# CW308T_STM32F415_Micro.net
KiCad netlist of a schematic drawn in Altium Designer
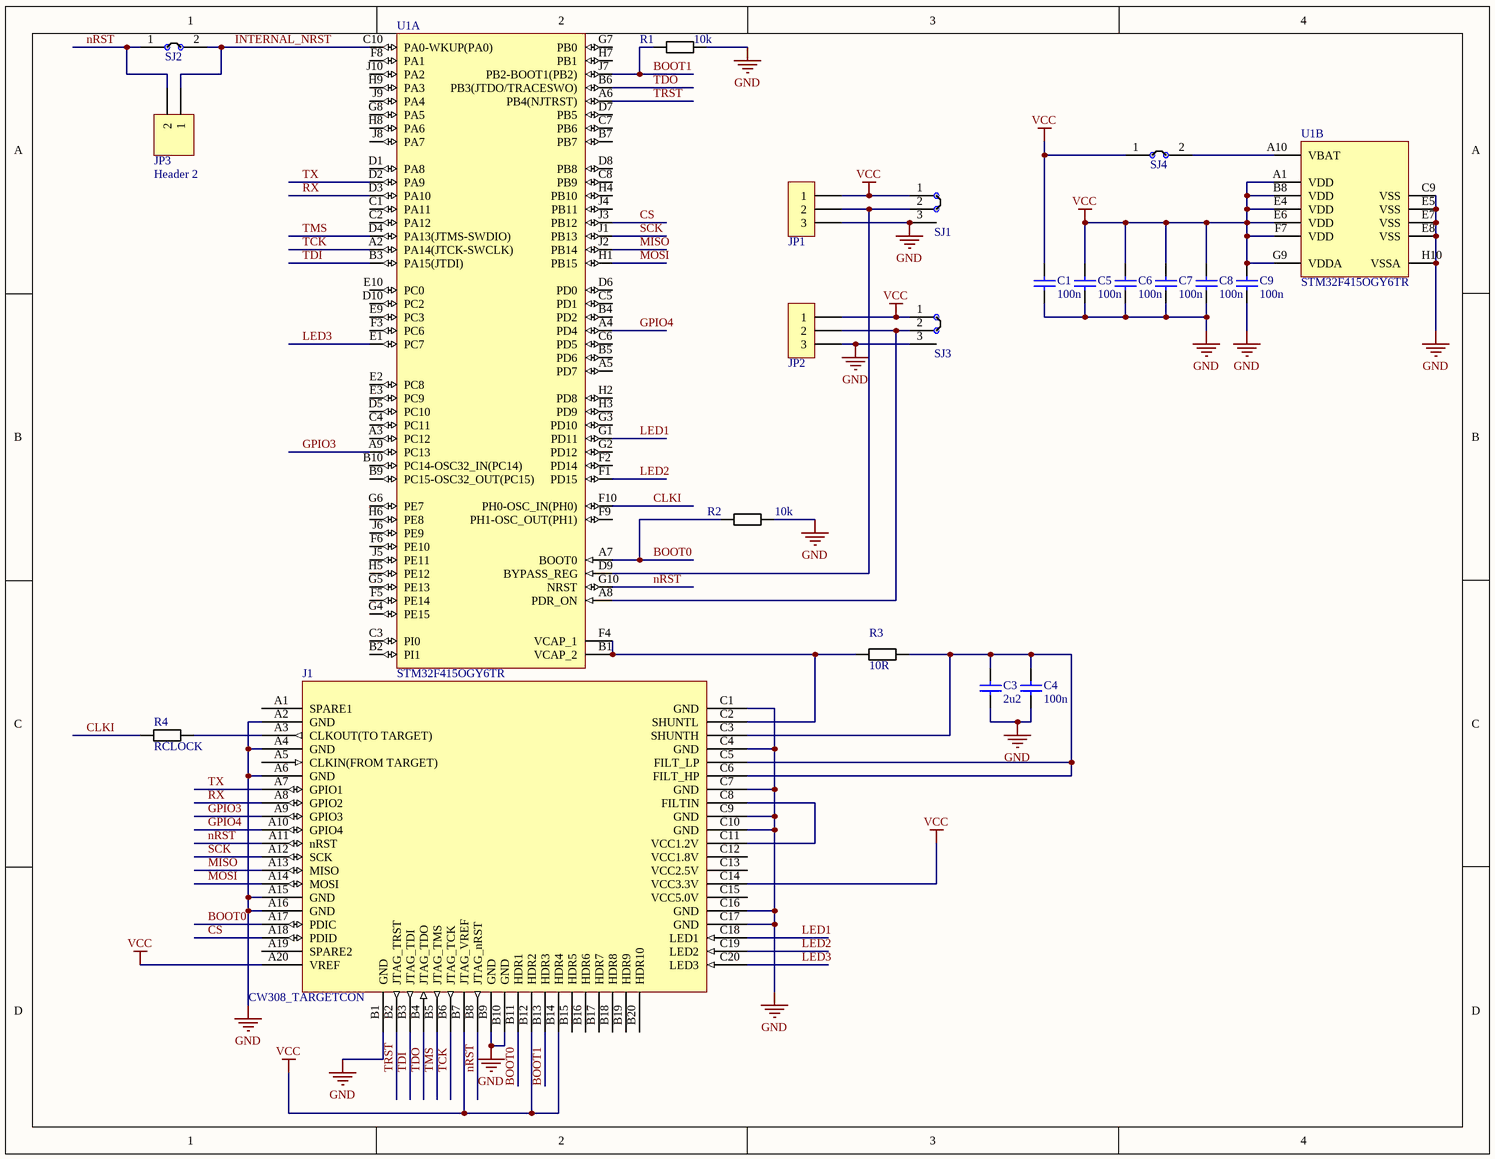
[diagram p0: CW308T_STM32F415_Micro.SchDoc]

(export (version "E")
  (design (tool "Eeschema 10.0.6"))
  (components
    (comp (ref "C1")
      (value "100n")
      (footprint "CAPC0603_M")
      (description "100n, 0603")
      (fields (field (name "PART NUMBER") "CCHIP-100n-0603"))
      (libsource (lib "NewAE_AltiumLib") (part "CAP"))
    )
    (comp (ref "C3")
      (value "2u2")
      (footprint "CAPC0603_M")
      (description "2u2, 0603")
      (fields (field (name "PART NUMBER") "CCHIP-2u2-0603"))
      (libsource (lib "NewAE_AltiumLib") (part "CAP"))
    )
    (comp (ref "C4")
      (value "100n")
      (footprint "CAPC0603_M")
      (description "100n, 0603")
      (fields (field (name "PART NUMBER") "CCHIP-100n-0603"))
      (libsource (lib "NewAE_AltiumLib") (part "CAP"))
    )
    (comp (ref "C5")
      (value "100n")
      (footprint "CAPC0603_M")
      (description "100n, 0603")
      (fields (field (name "PART NUMBER") "CCHIP-100n-0603"))
      (libsource (lib "NewAE_AltiumLib") (part "CAP"))
    )
    (comp (ref "C6")
      (value "100n")
      (footprint "CAPC0603_M")
      (description "100n, 0603")
      (fields (field (name "PART NUMBER") "CCHIP-100n-0603"))
      (libsource (lib "NewAE_AltiumLib") (part "CAP"))
    )
    (comp (ref "C7")
      (value "100n")
      (footprint "CAPC0603_M")
      (description "100n, 0603")
      (fields (field (name "PART NUMBER") "CCHIP-100n-0603"))
      (libsource (lib "NewAE_AltiumLib") (part "CAP"))
    )
    (comp (ref "C8")
      (value "100n")
      (footprint "CAPC0603_M")
      (description "100n, 0603")
      (fields (field (name "PART NUMBER") "CCHIP-100n-0603"))
      (libsource (lib "NewAE_AltiumLib") (part "CAP"))
    )
    (comp (ref "C9")
      (value "100n")
      (footprint "CAPC0603_M")
      (description "100n, 0603")
      (fields (field (name "PART NUMBER") "CCHIP-100n-0603"))
      (libsource (lib "NewAE_AltiumLib") (part "CAP"))
    )
    (comp (ref "J1")
      (value "CW308_TARGETCON")
      (footprint "CW308_SMD_TBOARD_CONN_BOTTOM")
      (description "CW308 \"Standard\" Target Board Connector")
      (fields (field (name "PART NUMBER") "CW308_TBOARD"))
      (libsource (lib "NewAE_AltiumLib") (part "CW308_TBOARD"))
    )
    (comp (ref "JP1")
      (value "Straight Header Pins")
      (footprint "1x3_SMD_Straight_pins")
      (description "1x3 Straight pin header")
      (fields (field (name "PART NUMBER") "HDR_3PIN"))
      (libsource (lib "NewAE_AltiumLib") (part "1x3_Pin_Header"))
    )
    (comp (ref "JP2")
      (value "Straight Header Pins")
      (footprint "1x3_SMD_Straight_pins")
      (description "1x3 Straight pin header")
      (fields (field (name "PART NUMBER") "HDR_3PIN"))
      (libsource (lib "NewAE_AltiumLib") (part "1x3_Pin_Header"))
    )
    (comp (ref "JP3")
      (value "Header 2")
      (footprint "1x2_SMD_Straight_pins")
      (description "Header, 2-Pin")
      (fields (field (name "PUBLISHER") "Altium Limited"))
      (libsource (lib "Miscellaneous Connectors") (part "Header 2"))
    )
    (comp (ref "R1")
      (value "10k")
      (footprint "RESC1608X55N")
      (description "10k res, 0603, 1%, 1/10W")
      (fields (field (name "PART NUMBER") "RCHIP-10K-0603") (field (name "TOLERANCE") "1%"))
      (libsource (lib "NewAE_AltiumLib") (part "RES-EU"))
    )
    (comp (ref "R2")
      (value "10k")
      (footprint "RESC1608X55N")
      (description "10k res, 0603, 1%, 1/10W")
      (fields (field (name "PART NUMBER") "RCHIP-10K-0603") (field (name "TOLERANCE") "1%"))
      (libsource (lib "NewAE_AltiumLib") (part "RES-EU"))
    )
    (comp (ref "R3")
      (value "10R")
      (footprint "RESC1608X55N")
      (description "10R res, 0603, 1%, 1/10W")
      (fields (field (name "PART NUMBER") "RCHIP-10R-0603") (field (name "TOLERANCE") "1%"))
      (libsource (lib "NewAE_AltiumLib") (part "RES-EU"))
    )
    (comp (ref "R4")
      (value "RCLOCK")
      (footprint "RESC1608X55N")
      (description "100R res, 0603, 1%, 1/10W")
      (fields (field (name "PART NUMBER") "RCHIP-100R-0603") (field (name "TOLERANCE") "1%"))
      (libsource (lib "NewAE_AltiumLib") (part "RES-EU"))
    )
    (comp (ref "SJ1")
      (value "NC")
      (footprint "SJ_3S_NC12")
      (description "Solder Jumper, NC")
      (fields (field (name "PART NUMBER") "SJ_3S_12JMP"))
      (libsource (lib "NewAE_AltiumLib") (part "SJ_3S_12JMP"))
    )
    (comp (ref "SJ2")
      (value "NC")
      (footprint "SJ_2S_NC")
      (description "Solder Jumper, NC")
      (fields (field (name "PART NUMBER") "SJ_2S"))
      (libsource (lib "NewAE_AltiumLib") (part "SJ_2S"))
    )
    (comp (ref "SJ3")
      (value "NC")
      (footprint "SJ_3S_NC12")
      (description "Solder Jumper, NC")
      (fields (field (name "PART NUMBER") "SJ_3S_12JMP"))
      (libsource (lib "NewAE_AltiumLib") (part "SJ_3S_12JMP"))
    )
    (comp (ref "SJ4")
      (value "NC")
      (footprint "SJ_2S_NC")
      (description "Solder Jumper, NC")
      (fields (field (name "PART NUMBER") "SJ_2S"))
      (libsource (lib "NewAE_AltiumLib") (part "SJ_2S"))
    )
    (comp (ref "U1")
      (value "STM32F415OGY6TR")
      (footprint "STM-WLCSP90")
      (fields (field (name "MANUFACTURER") "STMicroelectronics"))
      (libsource (lib "Altium Content Vault") (part "MC-ARM-STM32F4X5-GA90"))
    )
  )
  (nets
    (net (code "1") (name "/BOOT0") (class "Default")
      (node (ref "J1") (pin "A17") (pinfunction "PDIC_A17") (pintype "bidirectional"))
      (node (ref "J1") (pin "B11") (pinfunction "HDR1_B11") (pintype "passive"))
      (node (ref "R2") (pin "1") (pinfunction "1_1") (pintype "passive"))
      (node (ref "U1") (pin "A7") (pinfunction "BOOT0_A7") (pintype "input"))
    )
    (net (code "2") (name "/BOOT1") (class "Default")
      (node (ref "J1") (pin "B13") (pinfunction "HDR3_B13") (pintype "passive"))
      (node (ref "R1") (pin "1") (pinfunction "1_1") (pintype "passive"))
      (node (ref "U1") (pin "J7") (pinfunction "PB2-BOOT1(PB2)_J7") (pintype "bidirectional"))
    )
    (net (code "3") (name "/CLKI") (class "Default")
      (node (ref "R4") (pin "1") (pinfunction "1_1") (pintype "passive"))
      (node (ref "U1") (pin "F10") (pinfunction "PH0-OSC_IN(PH0)_F10") (pintype "bidirectional"))
    )
    (net (code "4") (name "/CS") (class "Default")
      (node (ref "J1") (pin "A18") (pinfunction "PDID_A18") (pintype "bidirectional"))
      (node (ref "U1") (pin "J3") (pinfunction "PB12_J3") (pintype "bidirectional"))
    )
    (net (code "5") (name "/GPIO3") (class "Default")
      (node (ref "J1") (pin "A9") (pinfunction "GPIO3_A9") (pintype "bidirectional"))
      (node (ref "U1") (pin "A9") (pinfunction "PC13_A9") (pintype "bidirectional"))
    )
    (net (code "6") (name "/GPIO4") (class "Default")
      (node (ref "J1") (pin "A10") (pinfunction "GPIO4_A10") (pintype "bidirectional"))
      (node (ref "U1") (pin "A4") (pinfunction "PD4_A4") (pintype "bidirectional"))
    )
    (net (code "7") (name "/INTERNAL_NRST") (class "Default")
      (node (ref "JP3") (pin "1") (pinfunction "1_1") (pintype "passive"))
      (node (ref "SJ2") (pin "2") (pinfunction "2_2") (pintype "passive"))
      (node (ref "U1") (pin "C10") (pinfunction "PA0-WKUP(PA0)_C10") (pintype "bidirectional"))
    )
    (net (code "8") (name "/LED1") (class "Default")
      (node (ref "J1") (pin "C18") (pinfunction "LED1_C18") (pintype "input"))
      (node (ref "U1") (pin "G1") (pinfunction "PD11_G1") (pintype "bidirectional"))
    )
    (net (code "9") (name "/LED2") (class "Default")
      (node (ref "J1") (pin "C19") (pinfunction "LED2_C19") (pintype "input"))
      (node (ref "U1") (pin "F1") (pinfunction "PD15_F1") (pintype "bidirectional"))
    )
    (net (code "10") (name "/LED3") (class "Default")
      (node (ref "J1") (pin "C20") (pinfunction "LED3_C20") (pintype "input"))
      (node (ref "U1") (pin "E1") (pinfunction "PC7_E1") (pintype "bidirectional"))
    )
    (net (code "11") (name "/MISO") (class "Default")
      (node (ref "J1") (pin "A13") (pinfunction "MISO_A13") (pintype "bidirectional"))
      (node (ref "U1") (pin "J2") (pinfunction "PB14_J2") (pintype "bidirectional"))
    )
    (net (code "12") (name "/MOSI") (class "Default")
      (node (ref "J1") (pin "A14") (pinfunction "MOSI_A14") (pintype "bidirectional"))
      (node (ref "U1") (pin "H1") (pinfunction "PB15_H1") (pintype "bidirectional"))
    )
    (net (code "13") (name "/RX") (class "Default")
      (node (ref "J1") (pin "A8") (pinfunction "GPIO2_A8") (pintype "bidirectional"))
      (node (ref "U1") (pin "D3") (pinfunction "PA10_D3") (pintype "bidirectional"))
    )
    (net (code "14") (name "/SCK") (class "Default")
      (node (ref "J1") (pin "A12") (pinfunction "SCK_A12") (pintype "bidirectional"))
      (node (ref "U1") (pin "J1") (pinfunction "PB13_J1") (pintype "bidirectional"))
    )
    (net (code "15") (name "/TCK") (class "Default")
      (node (ref "J1") (pin "B6") (pinfunction "JTAG_TCK_B6") (pintype "output"))
      (node (ref "U1") (pin "A2") (pinfunction "PA14(JTCK-SWCLK)_A2") (pintype "bidirectional"))
    )
    (net (code "16") (name "/TDI") (class "Default")
      (node (ref "J1") (pin "B3") (pinfunction "JTAG_TDI_B3") (pintype "output"))
      (node (ref "U1") (pin "B3") (pinfunction "PA15(JTDI)_B3") (pintype "bidirectional"))
    )
    (net (code "17") (name "/TDO") (class "Default")
      (node (ref "J1") (pin "B4") (pinfunction "JTAG_TDO_B4") (pintype "input"))
      (node (ref "U1") (pin "B6") (pinfunction "PB3(JTDO/TRACESWO)_B6") (pintype "bidirectional"))
    )
    (net (code "18") (name "/TMS") (class "Default")
      (node (ref "J1") (pin "B5") (pinfunction "JTAG_TMS_B5") (pintype "output"))
      (node (ref "U1") (pin "D4") (pinfunction "PA13(JTMS-SWDIO)_D4") (pintype "bidirectional"))
    )
    (net (code "19") (name "/TRST") (class "Default")
      (node (ref "J1") (pin "B2") (pinfunction "JTAG_TRST_B2") (pintype "output"))
      (node (ref "U1") (pin "A6") (pinfunction "PB4(NJTRST)_A6") (pintype "bidirectional"))
    )
    (net (code "20") (name "/TX") (class "Default")
      (node (ref "J1") (pin "A7") (pinfunction "GPIO1_A7") (pintype "bidirectional"))
      (node (ref "U1") (pin "D2") (pinfunction "PA9_D2") (pintype "bidirectional"))
    )
    (net (code "21") (name "/nRST") (class "Default")
      (node (ref "J1") (pin "A11") (pinfunction "nRST_A11") (pintype "bidirectional"))
      (node (ref "J1") (pin "B8") (pinfunction "JTAG_nRST_B8") (pintype "output"))
      (node (ref "JP3") (pin "2") (pinfunction "2_2") (pintype "passive"))
      (node (ref "SJ2") (pin "1") (pinfunction "1_1") (pintype "passive"))
      (node (ref "U1") (pin "G10") (pinfunction "NRST_G10") (pintype "bidirectional"))
    )
    (net (code "22") (name "GND") (class "Default")
      (node (ref "C1") (pin "2") (pinfunction "2_2") (pintype "passive"))
      (node (ref "C3") (pin "2") (pinfunction "2_2") (pintype "passive"))
      (node (ref "C4") (pin "2") (pinfunction "2_2") (pintype "passive"))
      (node (ref "C5") (pin "2") (pinfunction "2_2") (pintype "passive"))
      (node (ref "C6") (pin "2") (pinfunction "2_2") (pintype "passive"))
      (node (ref "C7") (pin "2") (pinfunction "2_2") (pintype "passive"))
      (node (ref "C8") (pin "2") (pinfunction "2_2") (pintype "passive"))
      (node (ref "C9") (pin "2") (pinfunction "2_2") (pintype "passive"))
      (node (ref "J1") (pin "A15") (pinfunction "GND_A15") (pintype "passive"))
      (node (ref "J1") (pin "A16") (pinfunction "GND_A16") (pintype "passive"))
      (node (ref "J1") (pin "A2") (pinfunction "GND_A2") (pintype "passive"))
      (node (ref "J1") (pin "A4") (pinfunction "GND_A4") (pintype "passive"))
      (node (ref "J1") (pin "A6") (pinfunction "GND_A6") (pintype "power_in"))
      (node (ref "J1") (pin "B1") (pinfunction "GND_B1") (pintype "passive"))
      (node (ref "J1") (pin "B10") (pinfunction "GND_B10") (pintype "passive"))
      (node (ref "J1") (pin "B9") (pinfunction "GND_B9") (pintype "passive"))
      (node (ref "J1") (pin "C1") (pinfunction "GND_C1") (pintype "power_in"))
      (node (ref "J1") (pin "C10") (pinfunction "GND_C10") (pintype "power_in"))
      (node (ref "J1") (pin "C16") (pinfunction "GND_C16") (pintype "power_in"))
      (node (ref "J1") (pin "C17") (pinfunction "GND_C17") (pintype "power_in"))
      (node (ref "J1") (pin "C4") (pinfunction "GND_C4") (pintype "power_in"))
      (node (ref "J1") (pin "C7") (pinfunction "GND_C7") (pintype "power_in"))
      (node (ref "J1") (pin "C9") (pinfunction "GND_C9") (pintype "power_in"))
      (node (ref "JP1") (pin "3") (pinfunction "3_3") (pintype "passive"))
      (node (ref "JP2") (pin "3") (pinfunction "3_3") (pintype "passive"))
      (node (ref "R1") (pin "2") (pinfunction "2_2") (pintype "passive"))
      (node (ref "R2") (pin "2") (pinfunction "2_2") (pintype "passive"))
      (node (ref "SJ1") (pin "3") (pinfunction "3_3") (pintype "passive"))
      (node (ref "SJ3") (pin "3") (pinfunction "3_3") (pintype "passive"))
      (node (ref "U1") (pin "C9") (pinfunction "VSS_C9") (pintype "power_in"))
      (node (ref "U1") (pin "E5") (pinfunction "VSS_E5") (pintype "power_in"))
      (node (ref "U1") (pin "E7") (pinfunction "VSS_E7") (pintype "power_in"))
      (node (ref "U1") (pin "E8") (pinfunction "VSS_E8") (pintype "power_in"))
      (node (ref "U1") (pin "H10") (pinfunction "VSSA_H10") (pintype "power_in"))
    )
    (net (code "23") (name "Net-(J1-CLKOUT(TO_TARGET))") (class "Default")
      (node (ref "J1") (pin "A3") (pinfunction "CLKOUT(TO_TARGET)_A3") (pintype "output"))
      (node (ref "R4") (pin "2") (pinfunction "2_2") (pintype "passive"))
    )
    (net (code "24") (name "Net-(J1-FILTIN)") (class "Default")
      (node (ref "J1") (pin "C11") (pinfunction "VCC1.2V_C11") (pintype "power_in"))
      (node (ref "J1") (pin "C8") (pinfunction "FILTIN_C8") (pintype "passive"))
    )
    (net (code "25") (name "Net-(J1-FILT_HP)") (class "Default")
      (node (ref "C3") (pin "1") (pinfunction "1_1") (pintype "passive"))
      (node (ref "C4") (pin "1") (pinfunction "1_1") (pintype "passive"))
      (node (ref "J1") (pin "C3") (pinfunction "SHUNTH_C3") (pintype "passive"))
      (node (ref "J1") (pin "C5") (pinfunction "FILT_LP_C5") (pintype "passive"))
      (node (ref "J1") (pin "C6") (pinfunction "FILT_HP_C6") (pintype "passive"))
      (node (ref "R3") (pin "2") (pinfunction "2_2") (pintype "passive"))
    )
    (net (code "26") (name "Net-(J1-SHUNTL)") (class "Default")
      (node (ref "J1") (pin "C2") (pinfunction "SHUNTL_C2") (pintype "passive"))
      (node (ref "R3") (pin "1") (pinfunction "1_1") (pintype "passive"))
      (node (ref "U1") (pin "B1") (pinfunction "VCAP_2_B1") (pintype "power_in"))
      (node (ref "U1") (pin "F4") (pinfunction "VCAP_1_F4") (pintype "power_in"))
    )
    (net (code "27") (name "Net-(U1A-BYPASS_REG)") (class "Default")
      (node (ref "JP1") (pin "2") (pinfunction "2_2") (pintype "passive"))
      (node (ref "SJ1") (pin "2") (pinfunction "2_2") (pintype "passive"))
      (node (ref "U1") (pin "D9") (pinfunction "BYPASS_REG_D9") (pintype "input"))
    )
    (net (code "28") (name "Net-(U1A-PDR_ON)") (class "Default")
      (node (ref "JP2") (pin "2") (pinfunction "2_2") (pintype "passive"))
      (node (ref "SJ3") (pin "2") (pinfunction "2_2") (pintype "passive"))
      (node (ref "U1") (pin "A8") (pinfunction "PDR_ON_A8") (pintype "input"))
    )
    (net (code "29") (name "Net-(U1B-VBAT)") (class "Default")
      (node (ref "SJ4") (pin "2") (pinfunction "2_2") (pintype "passive"))
      (node (ref "U1") (pin "A10") (pinfunction "VBAT_A10") (pintype "power_in"))
    )
    (net (code "30") (name "VCC") (class "Default")
      (node (ref "C1") (pin "1") (pinfunction "1_1") (pintype "passive"))
      (node (ref "C5") (pin "1") (pinfunction "1_1") (pintype "passive"))
      (node (ref "C6") (pin "1") (pinfunction "1_1") (pintype "passive"))
      (node (ref "C7") (pin "1") (pinfunction "1_1") (pintype "passive"))
      (node (ref "C8") (pin "1") (pinfunction "1_1") (pintype "passive"))
      (node (ref "C9") (pin "1") (pinfunction "1_1") (pintype "passive"))
      (node (ref "J1") (pin "A20") (pinfunction "VREF_A20") (pintype "tri_state"))
      (node (ref "J1") (pin "B12") (pinfunction "HDR2_B12") (pintype "passive"))
      (node (ref "J1") (pin "B14") (pinfunction "HDR4_B14") (pintype "passive"))
      (node (ref "J1") (pin "B7") (pinfunction "JTAG_VREF_B7") (pintype "tri_state"))
      (node (ref "J1") (pin "C14") (pinfunction "VCC3.3V_C14") (pintype "power_in"))
      (node (ref "JP1") (pin "1") (pinfunction "1_1") (pintype "passive"))
      (node (ref "JP2") (pin "1") (pinfunction "1_1") (pintype "passive"))
      (node (ref "SJ1") (pin "1") (pinfunction "1_1") (pintype "passive"))
      (node (ref "SJ3") (pin "1") (pinfunction "1_1") (pintype "passive"))
      (node (ref "SJ4") (pin "1") (pinfunction "1_1") (pintype "passive"))
      (node (ref "U1") (pin "A1") (pinfunction "VDD_A1") (pintype "power_in"))
      (node (ref "U1") (pin "B8") (pinfunction "VDD_B8") (pintype "power_in"))
      (node (ref "U1") (pin "E4") (pinfunction "VDD_E4") (pintype "power_in"))
      (node (ref "U1") (pin "E6") (pinfunction "VDD_E6") (pintype "power_in"))
      (node (ref "U1") (pin "F7") (pinfunction "VDD_F7") (pintype "power_in"))
      (node (ref "U1") (pin "G9") (pinfunction "VDDA_G9") (pintype "power_in"))
    )
    (net (code "31") (name "unconnected-(J1-CLKIN(FROM_TARGET)-PadA5)") (class "Default")
      (node (ref "J1") (pin "A5") (pinfunction "CLKIN(FROM_TARGET)_A5") (pintype "input"))
    )
    (net (code "32") (name "unconnected-(J1-HDR5-PadB15)") (class "Default")
      (node (ref "J1") (pin "B15") (pinfunction "HDR5_B15") (pintype "passive"))
    )
    (net (code "33") (name "unconnected-(J1-HDR6-PadB16)") (class "Default")
      (node (ref "J1") (pin "B16") (pinfunction "HDR6_B16") (pintype "passive"))
    )
    (net (code "34") (name "unconnected-(J1-HDR7-PadB17)") (class "Default")
      (node (ref "J1") (pin "B17") (pinfunction "HDR7_B17") (pintype "passive"))
    )
    (net (code "35") (name "unconnected-(J1-HDR8-PadB18)") (class "Default")
      (node (ref "J1") (pin "B18") (pinfunction "HDR8_B18") (pintype "passive"))
    )
    (net (code "36") (name "unconnected-(J1-HDR9-PadB19)") (class "Default")
      (node (ref "J1") (pin "B19") (pinfunction "HDR9_B19") (pintype "passive"))
    )
    (net (code "37") (name "unconnected-(J1-HDR10-PadB20)") (class "Default")
      (node (ref "J1") (pin "B20") (pinfunction "HDR10_B20") (pintype "passive"))
    )
    (net (code "38") (name "unconnected-(J1-SPARE1-PadA1)") (class "Default")
      (node (ref "J1") (pin "A1") (pinfunction "SPARE1_A1") (pintype "passive"))
    )
    (net (code "39") (name "unconnected-(J1-SPARE2-PadA19)") (class "Default")
      (node (ref "J1") (pin "A19") (pinfunction "SPARE2_A19") (pintype "passive"))
    )
    (net (code "40") (name "unconnected-(J1-VCC1.8V-PadC12)") (class "Default")
      (node (ref "J1") (pin "C12") (pinfunction "VCC1.8V_C12") (pintype "power_in"))
    )
    (net (code "41") (name "unconnected-(J1-VCC2.5V-PadC13)") (class "Default")
      (node (ref "J1") (pin "C13") (pinfunction "VCC2.5V_C13") (pintype "power_in"))
    )
    (net (code "42") (name "unconnected-(J1-VCC5.0V-PadC15)") (class "Default")
      (node (ref "J1") (pin "C15") (pinfunction "VCC5.0V_C15") (pintype "power_in"))
    )
    (net (code "43") (name "unconnected-(U1A-PA1-PadF8)") (class "Default")
      (node (ref "U1") (pin "F8") (pinfunction "PA1_F8") (pintype "bidirectional"))
    )
    (net (code "44") (name "unconnected-(U1A-PA2-PadJ10)") (class "Default")
      (node (ref "U1") (pin "J10") (pinfunction "PA2_J10") (pintype "bidirectional"))
    )
    (net (code "45") (name "unconnected-(U1A-PA3-PadH9)") (class "Default")
      (node (ref "U1") (pin "H9") (pinfunction "PA3_H9") (pintype "bidirectional"))
    )
    (net (code "46") (name "unconnected-(U1A-PA4-PadJ9)") (class "Default")
      (node (ref "U1") (pin "J9") (pinfunction "PA4_J9") (pintype "bidirectional"))
    )
    (net (code "47") (name "unconnected-(U1A-PA5-PadG8)") (class "Default")
      (node (ref "U1") (pin "G8") (pinfunction "PA5_G8") (pintype "bidirectional"))
    )
    (net (code "48") (name "unconnected-(U1A-PA6-PadH8)") (class "Default")
      (node (ref "U1") (pin "H8") (pinfunction "PA6_H8") (pintype "bidirectional"))
    )
    (net (code "49") (name "unconnected-(U1A-PA7-PadJ8)") (class "Default")
      (node (ref "U1") (pin "J8") (pinfunction "PA7_J8") (pintype "bidirectional"))
    )
    (net (code "50") (name "unconnected-(U1A-PA8-PadD1)") (class "Default")
      (node (ref "U1") (pin "D1") (pinfunction "PA8_D1") (pintype "bidirectional"))
    )
    (net (code "51") (name "unconnected-(U1A-PA11-PadC1)") (class "Default")
      (node (ref "U1") (pin "C1") (pinfunction "PA11_C1") (pintype "bidirectional"))
    )
    (net (code "52") (name "unconnected-(U1A-PA12-PadC2)") (class "Default")
      (node (ref "U1") (pin "C2") (pinfunction "PA12_C2") (pintype "bidirectional"))
    )
    (net (code "53") (name "unconnected-(U1A-PB0-PadG7)") (class "Default")
      (node (ref "U1") (pin "G7") (pinfunction "PB0_G7") (pintype "bidirectional"))
    )
    (net (code "54") (name "unconnected-(U1A-PB1-PadH7)") (class "Default")
      (node (ref "U1") (pin "H7") (pinfunction "PB1_H7") (pintype "bidirectional"))
    )
    (net (code "55") (name "unconnected-(U1A-PB5-PadD7)") (class "Default")
      (node (ref "U1") (pin "D7") (pinfunction "PB5_D7") (pintype "bidirectional"))
    )
    (net (code "56") (name "unconnected-(U1A-PB6-PadC7)") (class "Default")
      (node (ref "U1") (pin "C7") (pinfunction "PB6_C7") (pintype "bidirectional"))
    )
    (net (code "57") (name "unconnected-(U1A-PB7-PadB7)") (class "Default")
      (node (ref "U1") (pin "B7") (pinfunction "PB7_B7") (pintype "bidirectional"))
    )
    (net (code "58") (name "unconnected-(U1A-PB8-PadD8)") (class "Default")
      (node (ref "U1") (pin "D8") (pinfunction "PB8_D8") (pintype "bidirectional"))
    )
    (net (code "59") (name "unconnected-(U1A-PB9-PadC8)") (class "Default")
      (node (ref "U1") (pin "C8") (pinfunction "PB9_C8") (pintype "bidirectional"))
    )
    (net (code "60") (name "unconnected-(U1A-PB10-PadH4)") (class "Default")
      (node (ref "U1") (pin "H4") (pinfunction "PB10_H4") (pintype "bidirectional"))
    )
    (net (code "61") (name "unconnected-(U1A-PB11-PadJ4)") (class "Default")
      (node (ref "U1") (pin "J4") (pinfunction "PB11_J4") (pintype "bidirectional"))
    )
    (net (code "62") (name "unconnected-(U1A-PC0-PadE10)") (class "Default")
      (node (ref "U1") (pin "E10") (pinfunction "PC0_E10") (pintype "bidirectional"))
    )
    (net (code "63") (name "unconnected-(U1A-PC2-PadD10)") (class "Default")
      (node (ref "U1") (pin "D10") (pinfunction "PC2_D10") (pintype "bidirectional"))
    )
    (net (code "64") (name "unconnected-(U1A-PC3-PadE9)") (class "Default")
      (node (ref "U1") (pin "E9") (pinfunction "PC3_E9") (pintype "bidirectional"))
    )
    (net (code "65") (name "unconnected-(U1A-PC6-PadF3)") (class "Default")
      (node (ref "U1") (pin "F3") (pinfunction "PC6_F3") (pintype "bidirectional"))
    )
    (net (code "66") (name "unconnected-(U1A-PC8-PadE2)") (class "Default")
      (node (ref "U1") (pin "E2") (pinfunction "PC8_E2") (pintype "bidirectional"))
    )
    (net (code "67") (name "unconnected-(U1A-PC9-PadE3)") (class "Default")
      (node (ref "U1") (pin "E3") (pinfunction "PC9_E3") (pintype "bidirectional"))
    )
    (net (code "68") (name "unconnected-(U1A-PC10-PadD5)") (class "Default")
      (node (ref "U1") (pin "D5") (pinfunction "PC10_D5") (pintype "bidirectional"))
    )
    (net (code "69") (name "unconnected-(U1A-PC11-PadC4)") (class "Default")
      (node (ref "U1") (pin "C4") (pinfunction "PC11_C4") (pintype "bidirectional"))
    )
    (net (code "70") (name "unconnected-(U1A-PC12-PadA3)") (class "Default")
      (node (ref "U1") (pin "A3") (pinfunction "PC12_A3") (pintype "bidirectional"))
    )
    (net (code "71") (name "unconnected-(U1A-PC14-OSC32_IN(PC14)-PadB10)") (class "Default")
      (node (ref "U1") (pin "B10") (pinfunction "PC14-OSC32_IN(PC14)_B10") (pintype "bidirectional"))
    )
    (net (code "72") (name "unconnected-(U1A-PC15-OSC32_OUT(PC15)-PadB9)") (class "Default")
      (node (ref "U1") (pin "B9") (pinfunction "PC15-OSC32_OUT(PC15)_B9") (pintype "bidirectional"))
    )
    (net (code "73") (name "unconnected-(U1A-PD0-PadD6)") (class "Default")
      (node (ref "U1") (pin "D6") (pinfunction "PD0_D6") (pintype "bidirectional"))
    )
    (net (code "74") (name "unconnected-(U1A-PD1-PadC5)") (class "Default")
      (node (ref "U1") (pin "C5") (pinfunction "PD1_C5") (pintype "bidirectional"))
    )
    (net (code "75") (name "unconnected-(U1A-PD2-PadB4)") (class "Default")
      (node (ref "U1") (pin "B4") (pinfunction "PD2_B4") (pintype "bidirectional"))
    )
    (net (code "76") (name "unconnected-(U1A-PD5-PadC6)") (class "Default")
      (node (ref "U1") (pin "C6") (pinfunction "PD5_C6") (pintype "bidirectional"))
    )
    (net (code "77") (name "unconnected-(U1A-PD6-PadB5)") (class "Default")
      (node (ref "U1") (pin "B5") (pinfunction "PD6_B5") (pintype "bidirectional"))
    )
    (net (code "78") (name "unconnected-(U1A-PD7-PadA5)") (class "Default")
      (node (ref "U1") (pin "A5") (pinfunction "PD7_A5") (pintype "bidirectional"))
    )
    (net (code "79") (name "unconnected-(U1A-PD8-PadH2)") (class "Default")
      (node (ref "U1") (pin "H2") (pinfunction "PD8_H2") (pintype "bidirectional"))
    )
    (net (code "80") (name "unconnected-(U1A-PD9-PadH3)") (class "Default")
      (node (ref "U1") (pin "H3") (pinfunction "PD9_H3") (pintype "bidirectional"))
    )
    (net (code "81") (name "unconnected-(U1A-PD10-PadG3)") (class "Default")
      (node (ref "U1") (pin "G3") (pinfunction "PD10_G3") (pintype "bidirectional"))
    )
    (net (code "82") (name "unconnected-(U1A-PD12-PadG2)") (class "Default")
      (node (ref "U1") (pin "G2") (pinfunction "PD12_G2") (pintype "bidirectional"))
    )
    (net (code "83") (name "unconnected-(U1A-PD14-PadF2)") (class "Default")
      (node (ref "U1") (pin "F2") (pinfunction "PD14_F2") (pintype "bidirectional"))
    )
    (net (code "84") (name "unconnected-(U1A-PE7-PadG6)") (class "Default")
      (node (ref "U1") (pin "G6") (pinfunction "PE7_G6") (pintype "bidirectional"))
    )
    (net (code "85") (name "unconnected-(U1A-PE8-PadH6)") (class "Default")
      (node (ref "U1") (pin "H6") (pinfunction "PE8_H6") (pintype "bidirectional"))
    )
    (net (code "86") (name "unconnected-(U1A-PE9-PadJ6)") (class "Default")
      (node (ref "U1") (pin "J6") (pinfunction "PE9_J6") (pintype "bidirectional"))
    )
    (net (code "87") (name "unconnected-(U1A-PE10-PadF6)") (class "Default")
      (node (ref "U1") (pin "F6") (pinfunction "PE10_F6") (pintype "bidirectional"))
    )
    (net (code "88") (name "unconnected-(U1A-PE11-PadJ5)") (class "Default")
      (node (ref "U1") (pin "J5") (pinfunction "PE11_J5") (pintype "bidirectional"))
    )
    (net (code "89") (name "unconnected-(U1A-PE12-PadH5)") (class "Default")
      (node (ref "U1") (pin "H5") (pinfunction "PE12_H5") (pintype "bidirectional"))
    )
    (net (code "90") (name "unconnected-(U1A-PE13-PadG5)") (class "Default")
      (node (ref "U1") (pin "G5") (pinfunction "PE13_G5") (pintype "bidirectional"))
    )
    (net (code "91") (name "unconnected-(U1A-PE14-PadF5)") (class "Default")
      (node (ref "U1") (pin "F5") (pinfunction "PE14_F5") (pintype "bidirectional"))
    )
    (net (code "92") (name "unconnected-(U1A-PE15-PadG4)") (class "Default")
      (node (ref "U1") (pin "G4") (pinfunction "PE15_G4") (pintype "bidirectional"))
    )
    (net (code "93") (name "unconnected-(U1A-PH1-OSC_OUT(PH1)-PadF9)") (class "Default")
      (node (ref "U1") (pin "F9") (pinfunction "PH1-OSC_OUT(PH1)_F9") (pintype "bidirectional"))
    )
    (net (code "94") (name "unconnected-(U1A-PI0-PadC3)") (class "Default")
      (node (ref "U1") (pin "C3") (pinfunction "PI0_C3") (pintype "bidirectional"))
    )
    (net (code "95") (name "unconnected-(U1A-PI1-PadB2)") (class "Default")
      (node (ref "U1") (pin "B2") (pinfunction "PI1_B2") (pintype "bidirectional"))
    )
  )
)
